# TemperatureLogger.net
KiCad netlist of a schematic drawn in EAGLE
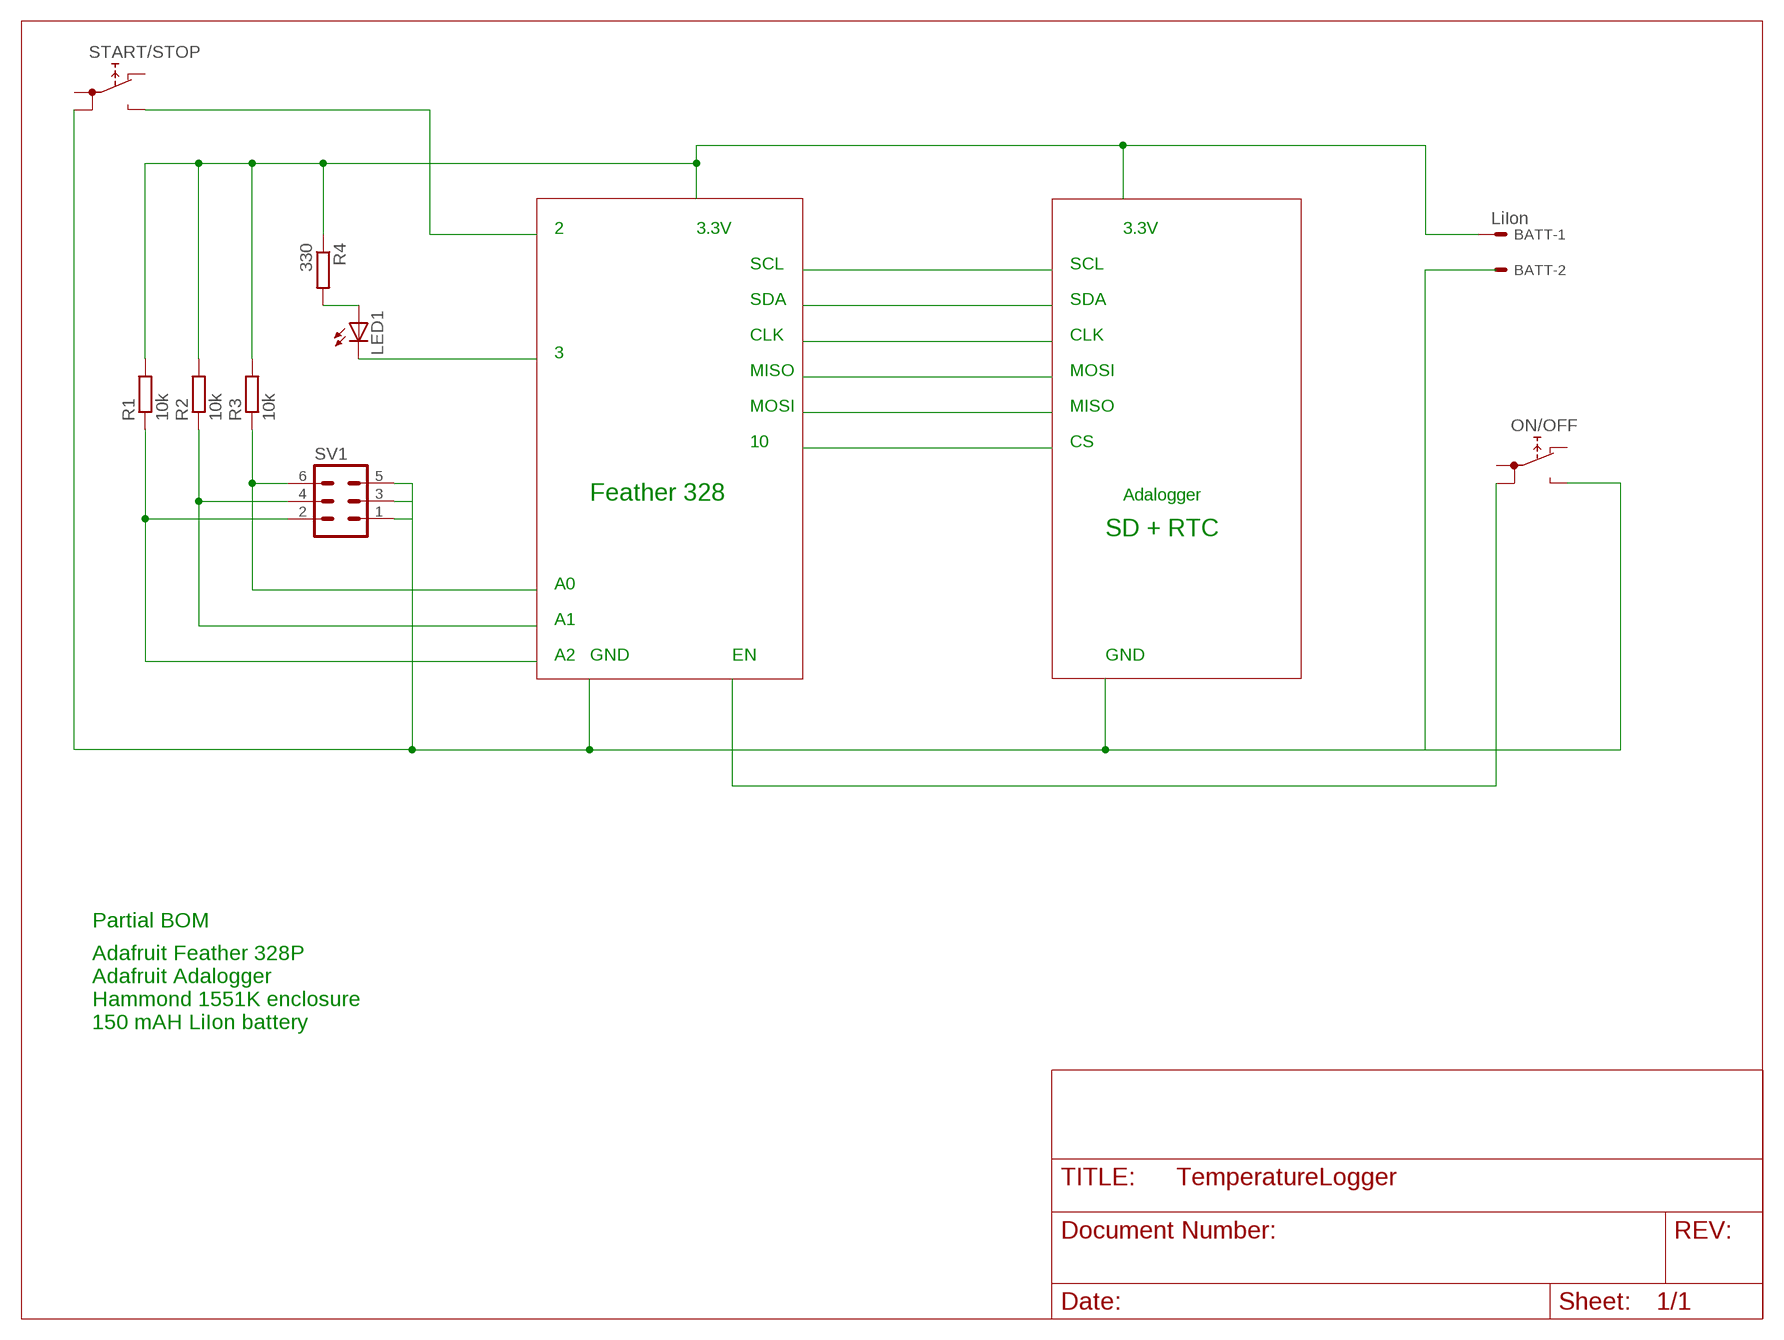
[diagram p0: schematic, sheet 1]

(export (version "E")
  (design (tool "Eeschema 10.0.6"))
  (components
    (comp (ref "BATT")
      (value "LiIon")
      (footprint "eagle-import:22-23-2021")
      (fields (field (name "MF") "MOLEX") (field (name "MPN") "22-23-2021"))
      (libsource (lib "eagle-import") (part "22-23-2021"))
    )
    (comp (ref "LED1")
      (value "LED")
      (footprint "eagle-import:SMARTLED-TTW")
      (libsource (lib "eagle-import") (part "LED"))
    )
    (comp (ref "ON/OFF")
      (value "5501")
      (footprint "eagle-import:5501")
      (libsource (lib "eagle-import") (part "55?01"))
    )
    (comp (ref "R1")
      (value "10k")
      (footprint "eagle-import:M0805")
      (libsource (lib "eagle-import") (part "R-EU_M0805"))
    )
    (comp (ref "R2")
      (value "10k")
      (footprint "eagle-import:M0805")
      (libsource (lib "eagle-import") (part "R-EU_M0805"))
    )
    (comp (ref "R3")
      (value "10k")
      (footprint "eagle-import:M0805")
      (libsource (lib "eagle-import") (part "R-EU_M0805"))
    )
    (comp (ref "R4")
      (value "330")
      (footprint "eagle-import:M0805")
      (libsource (lib "eagle-import") (part "R-EU_M0805"))
    )
    (comp (ref "START/STOP")
      (value "5501")
      (footprint "eagle-import:5501")
      (libsource (lib "eagle-import") (part "55?01"))
    )
    (comp (ref "SV1")
      (value "MA03-2")
      (footprint "eagle-import:MA03-2")
      (libsource (lib "eagle-import") (part "MA03-2"))
    )
  )
  (nets
    (net (code "1") (name "Net-(BATTA-S)") (class "Default")
      (node (ref "BATT") (pin "1") (pinfunction "S_1") (pintype "passive"))
      (node (ref "R1") (pin "2") (pinfunction "2_2") (pintype "passive"))
      (node (ref "R2") (pin "2") (pinfunction "2_2") (pintype "passive"))
      (node (ref "R3") (pin "2") (pinfunction "2_2") (pintype "passive"))
      (node (ref "R4") (pin "1") (pinfunction "1_1") (pintype "passive"))
    )
    (net (code "2") (name "Net-(LED1-A)") (class "Default")
      (node (ref "LED1") (pin "A@1") (pinfunction "A_A@1") (pintype "passive"))
      (node (ref "R4") (pin "2") (pinfunction "2_2") (pintype "passive"))
    )
    (net (code "3") (name "Net-(ON/OFF-PadNO)") (class "Default")
      (node (ref "ON/OFF") (pin "NO") (pinfunction "NO_NO") (pintype "passive"))
      (node (ref "START/STOP") (pin "1B") (pinfunction "1B_1B") (pintype "passive"))
      (node (ref "SV1") (pin "1") (pinfunction "1_1") (pintype "passive"))
      (node (ref "SV1") (pin "3") (pinfunction "3_3") (pintype "passive"))
      (node (ref "SV1") (pin "5") (pinfunction "5_5") (pintype "passive"))
    )
    (net (code "4") (name "Net-(R1-Pad1)") (class "Default")
      (node (ref "R1") (pin "1") (pinfunction "1_1") (pintype "passive"))
      (node (ref "SV1") (pin "2") (pinfunction "2_2") (pintype "passive"))
    )
    (net (code "5") (name "Net-(R2-Pad1)") (class "Default")
      (node (ref "R2") (pin "1") (pinfunction "1_1") (pintype "passive"))
      (node (ref "SV1") (pin "4") (pinfunction "4_4") (pintype "passive"))
    )
    (net (code "6") (name "Net-(R3-Pad1)") (class "Default")
      (node (ref "R3") (pin "1") (pinfunction "1_1") (pintype "passive"))
      (node (ref "SV1") (pin "6") (pinfunction "6_6") (pintype "passive"))
    )
    (net (code "7") (name "unconnected-(BATTB-S-Pad2)") (class "Default")
      (node (ref "BATT") (pin "2") (pinfunction "S_2") (pintype "passive"))
    )
    (net (code "8") (name "unconnected-(LED1-C-PadC@1)") (class "Default")
      (node (ref "LED1") (pin "C@1") (pinfunction "C_C@1") (pintype "passive"))
    )
    (net (code "9") (name "unconnected-(ON/OFF-Pad1A)") (class "Default")
      (node (ref "ON/OFF") (pin "1A") (pinfunction "1A_1A") (pintype "passive"))
    )
    (net (code "10") (name "unconnected-(ON/OFF-Pad1B)") (class "Default")
      (node (ref "ON/OFF") (pin "1B") (pinfunction "1B_1B") (pintype "passive"))
    )
    (net (code "11") (name "unconnected-(ON/OFF-PadNC)") (class "Default")
      (node (ref "ON/OFF") (pin "NC") (pinfunction "NC_NC") (pintype "passive"))
    )
    (net (code "12") (name "unconnected-(START/STOP-Pad1A)") (class "Default")
      (node (ref "START/STOP") (pin "1A") (pinfunction "1A_1A") (pintype "passive"))
    )
    (net (code "13") (name "unconnected-(START/STOP-PadNC)") (class "Default")
      (node (ref "START/STOP") (pin "NC") (pinfunction "NC_NC") (pintype "passive"))
    )
    (net (code "14") (name "unconnected-(START/STOP-PadNO)") (class "Default")
      (node (ref "START/STOP") (pin "NO") (pinfunction "NO_NO") (pintype "passive"))
    )
  )
)
